# 3_3v_regMod_AAT1217.net
KiCad netlist of a schematic drawn in EAGLE
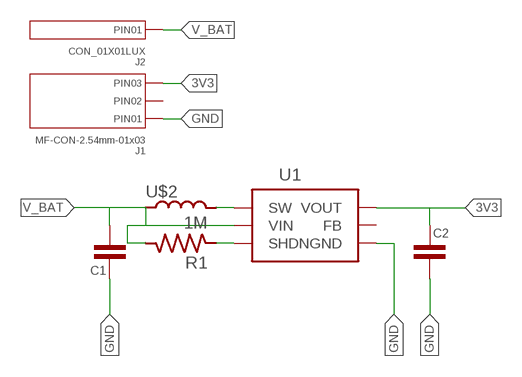
[diagram p0: schematic, sheet 1]

(export (version "E")
  (design (tool "Eeschema 10.0.6"))
  (components
    (comp (ref "C1")
      (value "CAPACITOR_NP0603-N")
      (footprint "eagle-import:C0603-N")
      (libsource (lib "eagle-import") (part "CAPACITOR_NP0603-N"))
    )
    (comp (ref "C2")
      (value "CAPACITOR_NP0603-N")
      (footprint "eagle-import:C0603-N")
      (libsource (lib "eagle-import") (part "CAPACITOR_NP0603-N"))
    )
    (comp (ref "J1")
      (value "MF-CON-2.54mm-01x03")
      (footprint "eagle-import:PTH_2.54MM_01X03")
      (fields (field (name "HOUSEPART") "YES"))
      (libsource (lib "eagle-import") (part "CON_01X03_PTH_2.54MM"))
    )
    (comp (ref "J2")
      (value "CON_01X01LUX")
      (footprint "eagle-import:1X01_LUXEON-PAD")
      (libsource (lib "eagle-import") (part "CON_01X01LUX"))
    )
    (comp (ref "R1")
      (value "1M")
      (footprint "eagle-import:R0603-N")
      (libsource (lib "eagle-import") (part "RESISTOR0603-N"))
    )
    (comp (ref "U$2")
      (value "INDUCTOR3030")
      (footprint "eagle-import:L3030")
      (libsource (lib "eagle-import") (part "INDUCTOR3030"))
    )
    (comp (ref "U1")
      (value "AAT1217-SOT23-6")
      (footprint "eagle-import:SOT23-6")
      (fields (field (name "PARTNO") "AAT1217ICA-3.3-T1"))
      (libsource (lib "eagle-import") (part "AAT1217-SOT23-6"))
    )
  )
  (nets
    (net (code "1") (name "3V3") (class "Default")
      (node (ref "C2") (pin "1") (pinfunction "1_1") (pintype "passive"))
      (node (ref "J1") (pin "P$3") (pinfunction "PIN3_P$3") (pintype "bidirectional"))
      (node (ref "U1") (pin "5") (pinfunction "VOUT_5") (pintype "bidirectional"))
    )
    (net (code "2") (name "GND") (class "Default")
      (node (ref "C1") (pin "1") (pinfunction "1_1") (pintype "passive"))
      (node (ref "C2") (pin "2") (pinfunction "2_2") (pintype "passive"))
      (node (ref "J1") (pin "P$1") (pinfunction "PIN1_P$1") (pintype "bidirectional"))
      (node (ref "U1") (pin "2") (pinfunction "GND_2") (pintype "bidirectional"))
    )
    (net (code "3") (name "Net-(R1-P$1)") (class "Default")
      (node (ref "R1") (pin "1") (pinfunction "P$1_1") (pintype "passive"))
      (node (ref "U1") (pin "4") (pinfunction "SHDN_4") (pintype "bidirectional"))
    )
    (net (code "4") (name "Net-(U1-SW)") (class "Default")
      (node (ref "U$2") (pin "P$2") (pinfunction "P$2_P$2") (pintype "passive"))
      (node (ref "U1") (pin "1") (pinfunction "SW_1") (pintype "bidirectional"))
    )
    (net (code "5") (name "V_BAT") (class "Default")
      (node (ref "C1") (pin "2") (pinfunction "2_2") (pintype "passive"))
      (node (ref "J2") (pin "P$1") (pinfunction "PIN1_P$1") (pintype "bidirectional"))
      (node (ref "R1") (pin "2") (pinfunction "P$2_2") (pintype "passive"))
      (node (ref "U$2") (pin "P$1") (pinfunction "P$1_P$1") (pintype "passive"))
      (node (ref "U1") (pin "6") (pinfunction "VIN_6") (pintype "bidirectional"))
    )
    (net (code "6") (name "unconnected-(J1-PIN2-PadP$2)") (class "Default")
      (node (ref "J1") (pin "P$2") (pinfunction "PIN2_P$2") (pintype "bidirectional"))
    )
    (net (code "7") (name "unconnected-(U1-FB-Pad3)") (class "Default")
      (node (ref "U1") (pin "3") (pinfunction "FB_3") (pintype "bidirectional"))
    )
  )
)
